# USB_Ethernet.net
KiCad netlist of a schematic drawn in Altium Designer
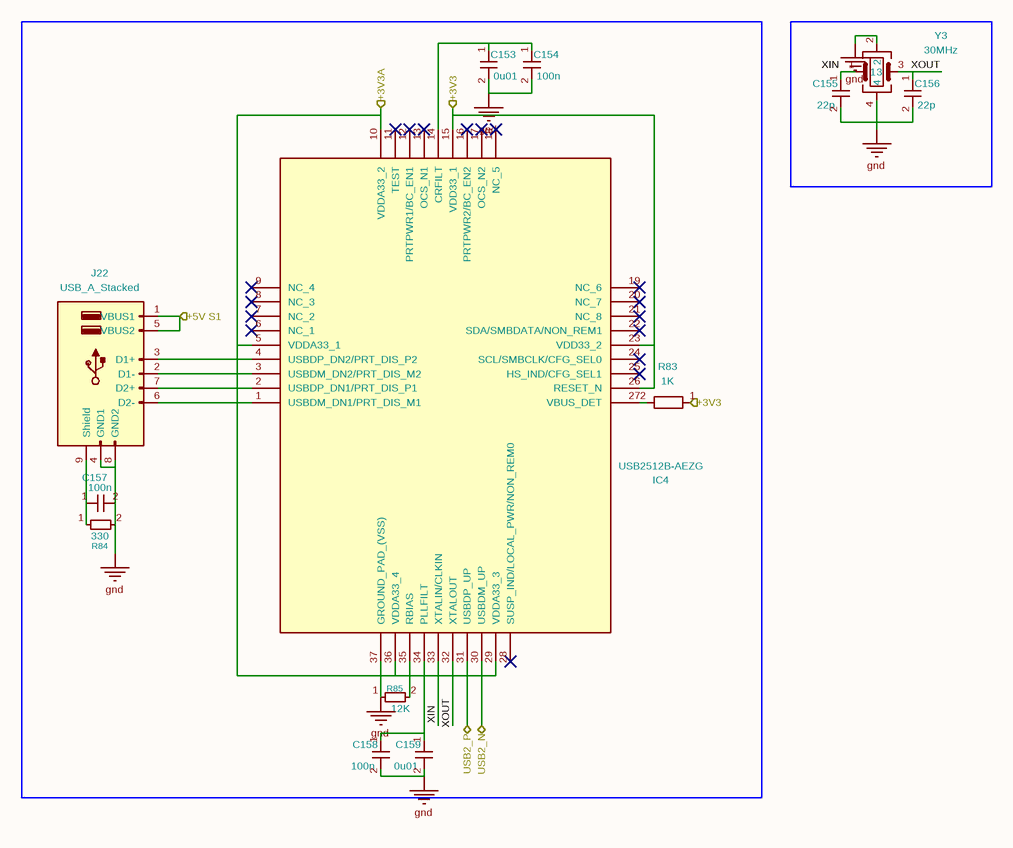
[diagram p0: USB & Ethernet.SchDoc]

(export (version "E")
  (design (tool "Eeschema 10.0.6"))
  (components
    (comp (ref "C153")
      (value "0u01")
      (description "Unpolarized capacitor, small symbol")
      (libsource (lib "Device") (part "C_Small"))
    )
    (comp (ref "C154")
      (value "100n")
      (description "Unpolarized capacitor, small symbol")
      (libsource (lib "Device") (part "C_Small"))
    )
    (comp (ref "C155")
      (value "22p")
      (description "Unpolarized capacitor, small symbol")
      (libsource (lib "Device") (part "C_Small"))
    )
    (comp (ref "C156")
      (value "22p")
      (description "Unpolarized capacitor, small symbol")
      (libsource (lib "Device") (part "C_Small"))
    )
    (comp (ref "C157")
      (value "100n")
      (description "Unpolarized capacitor, small symbol")
      (libsource (lib "Device") (part "C_Small"))
    )
    (comp (ref "C158")
      (value "100n")
      (description "Unpolarized capacitor, small symbol")
      (libsource (lib "Device") (part "C_Small"))
    )
    (comp (ref "C159")
      (value "0u01")
      (description "Unpolarized capacitor, small symbol")
      (libsource (lib "Device") (part "C_Small"))
    )
    (comp (ref "IC4")
      (value "USB2512B-AEZG")
      (fields (field (name "MOUSER PART NUMBER") "886-USB2512B-AEZG"))
      (libsource (lib "USB2512B-AEZG") (part "USB2512B-AEZG"))
    )
    (comp (ref "J22")
      (value "USB_A_Stacked")
      (description "USB Type A connector, stacked")
      (libsource (lib "Connector") (part "USB_A_Stacked"))
    )
    (comp (ref "R83") (value "1K") (description "Resistor") (libsource (lib "Device") (part "R")))
    (comp (ref "R84")
      (value "330")
      (description "Resistor, small symbol")
      (libsource (lib "Device") (part "R_Small"))
    )
    (comp (ref "R85")
      (value "12K")
      (description "Resistor, small symbol")
      (libsource (lib "Device") (part "R_Small"))
    )
    (comp (ref "Y3")
      (value "30MHz")
      (description "Four pin crystal, GND on pins 2 and 4")
      (libsource (lib "Device") (part "Crystal_GND24"))
    )
  )
  (nets
    (net (code "1") (name "/+3V3") (class "Default")
      (node (ref "IC4") (pin "15") (pinfunction "VDD33_1_15") (pintype "passive"))
      (node (ref "IC4") (pin "23") (pinfunction "VDD33_2_23") (pintype "passive"))
      (node (ref "IC4") (pin "26") (pinfunction "RESET_N_26") (pintype "passive"))
      (node (ref "R83") (pin "1") (pinfunction "1_1") (pintype "passive"))
    )
    (net (code "2") (name "/+3V3A") (class "Default")
      (node (ref "IC4") (pin "10") (pinfunction "VDDA33_2_10") (pintype "passive"))
      (node (ref "IC4") (pin "29") (pinfunction "VDDA33_3_29") (pintype "passive"))
      (node (ref "IC4") (pin "36") (pinfunction "VDDA33_4_36") (pintype "passive"))
      (node (ref "IC4") (pin "5") (pinfunction "VDDA33_1_5") (pintype "passive"))
    )
    (net (code "3") (name "/+5V S1") (class "Default")
      (node (ref "J22") (pin "1") (pinfunction "VBUS1_1") (pintype "passive"))
      (node (ref "J22") (pin "5") (pinfunction "VBUS2_5") (pintype "passive"))
    )
    (net (code "4") (name "/USB2_N") (class "Default")
      (node (ref "IC4") (pin "30") (pinfunction "USBDM_UP_30") (pintype "passive"))
    )
    (net (code "5") (name "/USB2_P") (class "Default")
      (node (ref "IC4") (pin "31") (pinfunction "USBDP_UP_31") (pintype "passive"))
    )
    (net (code "6") (name "/XIN") (class "Default")
      (node (ref "C155") (pin "1") (pinfunction "1_1") (pintype "passive"))
      (node (ref "IC4") (pin "33") (pinfunction "XTALIN/CLKIN_33") (pintype "passive"))
      (node (ref "Y3") (pin "1") (pinfunction "1_1") (pintype "passive"))
    )
    (net (code "7") (name "/XOUT") (class "Default")
      (node (ref "C156") (pin "1") (pinfunction "1_1") (pintype "passive"))
      (node (ref "IC4") (pin "32") (pinfunction "XTALOUT_32") (pintype "passive"))
      (node (ref "Y3") (pin "3") (pinfunction "3_3") (pintype "passive"))
    )
    (net (code "8") (name "Net-(IC4-CRFILT)") (class "Default")
      (node (ref "C153") (pin "1") (pinfunction "1_1") (pintype "passive"))
      (node (ref "C154") (pin "1") (pinfunction "1_1") (pintype "passive"))
      (node (ref "IC4") (pin "14") (pinfunction "CRFILT_14") (pintype "passive"))
    )
    (net (code "9") (name "Net-(IC4-PLLFILT)") (class "Default")
      (node (ref "C158") (pin "1") (pinfunction "1_1") (pintype "passive"))
      (node (ref "C159") (pin "1") (pinfunction "1_1") (pintype "passive"))
      (node (ref "IC4") (pin "34") (pinfunction "PLLFILT_34") (pintype "passive"))
    )
    (net (code "10") (name "Net-(IC4-RBIAS)") (class "Default")
      (node (ref "IC4") (pin "35") (pinfunction "RBIAS_35") (pintype "passive"))
      (node (ref "R85") (pin "2") (pinfunction "2_2") (pintype "passive"))
    )
    (net (code "11") (name "Net-(IC4-USBDM_DN1{slash}PRT_DIS_M1)") (class "Default")
      (node (ref "IC4") (pin "1") (pinfunction "USBDM_DN1/PRT_DIS_M1_1") (pintype "passive"))
      (node (ref "J22") (pin "6") (pinfunction "D2-_6") (pintype "passive"))
    )
    (net (code "12") (name "Net-(IC4-USBDM_DN2{slash}PRT_DIS_M2)") (class "Default")
      (node (ref "IC4") (pin "3") (pinfunction "USBDM_DN2/PRT_DIS_M2_3") (pintype "passive"))
      (node (ref "J22") (pin "2") (pinfunction "D1-_2") (pintype "passive"))
    )
    (net (code "13") (name "Net-(IC4-USBDP_DN1{slash}PRT_DIS_P1)") (class "Default")
      (node (ref "IC4") (pin "2") (pinfunction "USBDP_DN1/PRT_DIS_P1_2") (pintype "passive"))
      (node (ref "J22") (pin "7") (pinfunction "D2+_7") (pintype "passive"))
    )
    (net (code "14") (name "Net-(IC4-USBDP_DN2{slash}PRT_DIS_P2)") (class "Default")
      (node (ref "IC4") (pin "4") (pinfunction "USBDP_DN2/PRT_DIS_P2_4") (pintype "passive"))
      (node (ref "J22") (pin "3") (pinfunction "D1+_3") (pintype "passive"))
    )
    (net (code "15") (name "Net-(IC4-VBUS_DET)") (class "Default")
      (node (ref "IC4") (pin "27") (pinfunction "VBUS_DET_27") (pintype "passive"))
      (node (ref "R83") (pin "2") (pinfunction "2_2") (pintype "passive"))
    )
    (net (code "16") (name "Net-(J22-Shield)") (class "Default")
      (node (ref "C157") (pin "1") (pinfunction "1_1") (pintype "passive"))
      (node (ref "J22") (pin "9") (pinfunction "Shield_9") (pintype "passive"))
      (node (ref "R84") (pin "1") (pinfunction "1_1") (pintype "passive"))
    )
    (net (code "17") (name "gnd") (class "Default")
      (node (ref "C153") (pin "2") (pinfunction "2_2") (pintype "passive"))
      (node (ref "C154") (pin "2") (pinfunction "2_2") (pintype "passive"))
      (node (ref "C155") (pin "2") (pinfunction "2_2") (pintype "passive"))
      (node (ref "C156") (pin "2") (pinfunction "2_2") (pintype "passive"))
      (node (ref "C157") (pin "2") (pinfunction "2_2") (pintype "passive"))
      (node (ref "C158") (pin "2") (pinfunction "2_2") (pintype "passive"))
      (node (ref "C159") (pin "2") (pinfunction "2_2") (pintype "passive"))
      (node (ref "IC4") (pin "37") (pinfunction "GROUND_PAD_(VSS)_37") (pintype "passive"))
      (node (ref "J22") (pin "4") (pinfunction "GND1_4") (pintype "passive"))
      (node (ref "J22") (pin "8") (pinfunction "GND2_8") (pintype "passive"))
      (node (ref "R84") (pin "2") (pinfunction "2_2") (pintype "passive"))
      (node (ref "R85") (pin "1") (pinfunction "1_1") (pintype "passive"))
      (node (ref "Y3") (pin "2") (pinfunction "2_2") (pintype "passive"))
      (node (ref "Y3") (pin "4") (pinfunction "4_4") (pintype "passive"))
    )
    (net (code "18") (name "unconnected-(IC4-HS_IND{slash}CFG_SEL1-Pad25)") (class "Default")
      (node (ref "IC4") (pin "25") (pinfunction "HS_IND/CFG_SEL1_25") (pintype "passive+no_connect"))
    )
    (net (code "19") (name "unconnected-(IC4-NC_1-Pad6)") (class "Default")
      (node (ref "IC4") (pin "6") (pinfunction "NC_1_6") (pintype "passive+no_connect"))
    )
    (net (code "20") (name "unconnected-(IC4-NC_2-Pad7)") (class "Default")
      (node (ref "IC4") (pin "7") (pinfunction "NC_2_7") (pintype "passive+no_connect"))
    )
    (net (code "21") (name "unconnected-(IC4-NC_3-Pad8)") (class "Default")
      (node (ref "IC4") (pin "8") (pinfunction "NC_3_8") (pintype "passive+no_connect"))
    )
    (net (code "22") (name "unconnected-(IC4-NC_4-Pad9)") (class "Default")
      (node (ref "IC4") (pin "9") (pinfunction "NC_4_9") (pintype "passive+no_connect"))
    )
    (net (code "23") (name "unconnected-(IC4-NC_5-Pad18)") (class "Default")
      (node (ref "IC4") (pin "18") (pinfunction "NC_5_18") (pintype "passive+no_connect"))
    )
    (net (code "24") (name "unconnected-(IC4-NC_6-Pad19)") (class "Default")
      (node (ref "IC4") (pin "19") (pinfunction "NC_6_19") (pintype "passive+no_connect"))
    )
    (net (code "25") (name "unconnected-(IC4-NC_7-Pad20)") (class "Default")
      (node (ref "IC4") (pin "20") (pinfunction "NC_7_20") (pintype "passive+no_connect"))
    )
    (net (code "26") (name "unconnected-(IC4-NC_8-Pad21)") (class "Default")
      (node (ref "IC4") (pin "21") (pinfunction "NC_8_21") (pintype "passive+no_connect"))
    )
    (net (code "27") (name "unconnected-(IC4-OCS_N1-Pad13)") (class "Default")
      (node (ref "IC4") (pin "13") (pinfunction "OCS_N1_13") (pintype "passive+no_connect"))
    )
    (net (code "28") (name "unconnected-(IC4-OCS_N2-Pad17)") (class "Default")
      (node (ref "IC4") (pin "17") (pinfunction "OCS_N2_17") (pintype "passive+no_connect"))
    )
    (net (code "29") (name "unconnected-(IC4-PRTPWR1{slash}BC_EN1-Pad12)") (class "Default")
      (node (ref "IC4") (pin "12") (pinfunction "PRTPWR1/BC_EN1_12") (pintype "passive+no_connect"))
    )
    (net (code "30") (name "unconnected-(IC4-PRTPWR2{slash}BC_EN2-Pad16)") (class "Default")
      (node (ref "IC4") (pin "16") (pinfunction "PRTPWR2/BC_EN2_16") (pintype "passive+no_connect"))
    )
    (net (code "31") (name "unconnected-(IC4-SCL{slash}SMBCLK{slash}CFG_SEL0-Pad24)") (class "Default")
      (node (ref "IC4") (pin "24") (pinfunction "SCL/SMBCLK/CFG_SEL0_24") (pintype "passive+no_connect"))
    )
    (net (code "32") (name "unconnected-(IC4-SDA{slash}SMBDATA{slash}NON_REM1-Pad22)") (class "Default")
      (node (ref "IC4") (pin "22") (pinfunction "SDA/SMBDATA/NON_REM1_22") (pintype "passive+no_connect"))
    )
    (net (code "33") (name "unconnected-(IC4-SUSP_IND{slash}LOCAL_PWR{slash}NON_REM0-Pad28)") (class "Default")
      (node (ref "IC4") (pin "28") (pinfunction "SUSP_IND/LOCAL_PWR/NON_REM0_28") (pintype "passive+no_connect"))
    )
    (net (code "34") (name "unconnected-(IC4-TEST-Pad11)") (class "Default")
      (node (ref "IC4") (pin "11") (pinfunction "TEST_11") (pintype "passive+no_connect"))
    )
  )
)
